# Doug.net
KiCad netlist of a schematic drawn in EAGLE
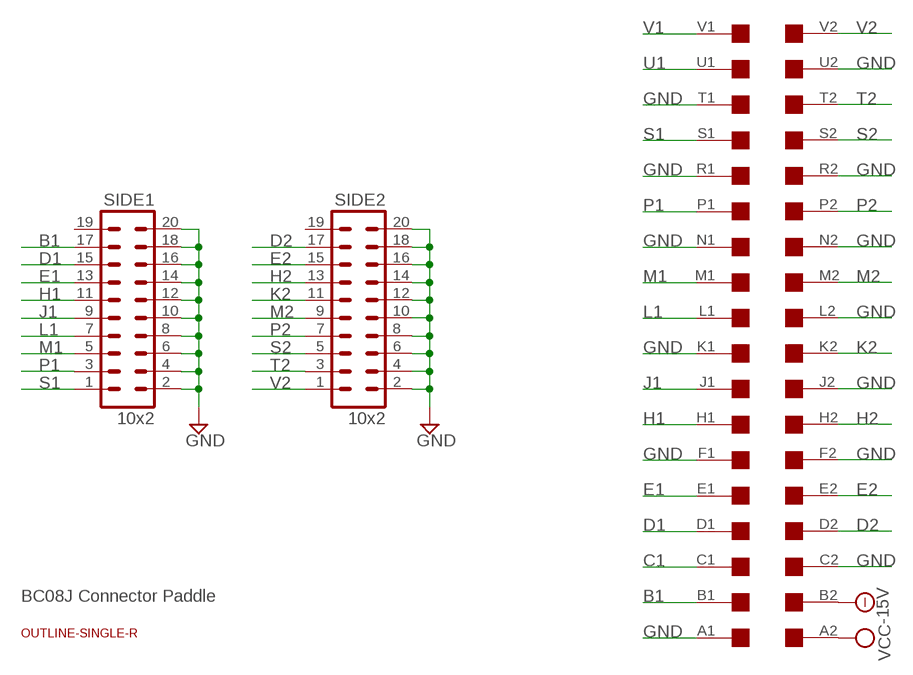
[diagram p0: schematic, sheet 1]

(export (version "E")
  (design (tool "Eeschema 10.0.6"))
  (components
    (comp (ref "SIDE1")
      (value "10x2")
      (footprint "eagle-import:MA10-2")
      (libsource (lib "eagle-import") (part "MA10-2"))
    )
    (comp (ref "SIDE2")
      (value "10x2")
      (footprint "eagle-import:MA10-2")
      (libsource (lib "eagle-import") (part "MA10-2"))
    )
    (comp (ref "U$1")
      (value "OUTLINE-SINGLE-R")
      (footprint "eagle-import:SINGLE-R")
      (libsource (lib "eagle-import") (part "OUTLINE-SINGLE-R"))
    )
    (comp (ref "U$2")
      (value "EDGE")
      (footprint "eagle-import:EDGE-CON2")
      (libsource (lib "eagle-import") (part "SINGLE"))
    )
  )
  (nets
    (net (code "1") (name "-15V") (class "Default")
      (node (ref "U$2") (pin "B2") (pinfunction "1_B2") (pintype "bidirectional"))
    )
    (net (code "2") (name "/B1") (class "Default")
      (node (ref "SIDE1") (pin "17") (pinfunction "17_17") (pintype "passive"))
      (node (ref "U$2") (pin "B1") (pinfunction "1_B1") (pintype "bidirectional"))
    )
    (net (code "3") (name "/C1") (class "Default")
      (node (ref "U$2") (pin "C1") (pinfunction "1_C1") (pintype "bidirectional"))
    )
    (net (code "4") (name "/D1") (class "Default")
      (node (ref "SIDE1") (pin "15") (pinfunction "15_15") (pintype "passive"))
      (node (ref "U$2") (pin "D1") (pinfunction "1_D1") (pintype "bidirectional"))
    )
    (net (code "5") (name "/D2") (class "Default")
      (node (ref "SIDE2") (pin "17") (pinfunction "17_17") (pintype "passive"))
      (node (ref "U$2") (pin "D2") (pinfunction "1_D2") (pintype "bidirectional"))
    )
    (net (code "6") (name "/E1") (class "Default")
      (node (ref "SIDE1") (pin "13") (pinfunction "13_13") (pintype "passive"))
      (node (ref "U$2") (pin "E1") (pinfunction "1_E1") (pintype "bidirectional"))
    )
    (net (code "7") (name "/E2") (class "Default")
      (node (ref "SIDE2") (pin "15") (pinfunction "15_15") (pintype "passive"))
      (node (ref "U$2") (pin "E2") (pinfunction "1_E2") (pintype "bidirectional"))
    )
    (net (code "8") (name "/H1") (class "Default")
      (node (ref "SIDE1") (pin "11") (pinfunction "11_11") (pintype "passive"))
      (node (ref "U$2") (pin "H1") (pinfunction "1_H1") (pintype "bidirectional"))
    )
    (net (code "9") (name "/H2") (class "Default")
      (node (ref "SIDE2") (pin "13") (pinfunction "13_13") (pintype "passive"))
      (node (ref "U$2") (pin "H2") (pinfunction "1_H2") (pintype "bidirectional"))
    )
    (net (code "10") (name "/J1") (class "Default")
      (node (ref "SIDE1") (pin "9") (pinfunction "9_9") (pintype "passive"))
      (node (ref "U$2") (pin "J1") (pinfunction "1_J1") (pintype "bidirectional"))
    )
    (net (code "11") (name "/K2") (class "Default")
      (node (ref "SIDE2") (pin "11") (pinfunction "11_11") (pintype "passive"))
      (node (ref "U$2") (pin "K2") (pinfunction "1_K2") (pintype "bidirectional"))
    )
    (net (code "12") (name "/L1") (class "Default")
      (node (ref "SIDE1") (pin "7") (pinfunction "7_7") (pintype "passive"))
      (node (ref "U$2") (pin "L1") (pinfunction "1_L1") (pintype "bidirectional"))
    )
    (net (code "13") (name "/M1") (class "Default")
      (node (ref "SIDE1") (pin "5") (pinfunction "5_5") (pintype "passive"))
      (node (ref "U$2") (pin "M1") (pinfunction "1_M1") (pintype "bidirectional"))
    )
    (net (code "14") (name "/M2") (class "Default")
      (node (ref "SIDE2") (pin "9") (pinfunction "9_9") (pintype "passive"))
      (node (ref "U$2") (pin "M2") (pinfunction "1_M2") (pintype "bidirectional"))
    )
    (net (code "15") (name "/P1") (class "Default")
      (node (ref "SIDE1") (pin "3") (pinfunction "3_3") (pintype "passive"))
      (node (ref "U$2") (pin "P1") (pinfunction "1_P1") (pintype "bidirectional"))
    )
    (net (code "16") (name "/P2") (class "Default")
      (node (ref "SIDE2") (pin "7") (pinfunction "7_7") (pintype "passive"))
      (node (ref "U$2") (pin "P2") (pinfunction "1_P2") (pintype "bidirectional"))
    )
    (net (code "17") (name "/S1") (class "Default")
      (node (ref "SIDE1") (pin "1") (pinfunction "1_1") (pintype "passive"))
      (node (ref "U$2") (pin "S1") (pinfunction "1_S1") (pintype "bidirectional"))
    )
    (net (code "18") (name "/S2") (class "Default")
      (node (ref "SIDE2") (pin "5") (pinfunction "5_5") (pintype "passive"))
      (node (ref "U$2") (pin "S2") (pinfunction "1_S2") (pintype "bidirectional"))
    )
    (net (code "19") (name "/T2") (class "Default")
      (node (ref "SIDE2") (pin "3") (pinfunction "3_3") (pintype "passive"))
      (node (ref "U$2") (pin "T2") (pinfunction "1_T2") (pintype "bidirectional"))
    )
    (net (code "20") (name "/U1") (class "Default")
      (node (ref "U$2") (pin "U1") (pinfunction "1_U1") (pintype "bidirectional"))
    )
    (net (code "21") (name "/V1") (class "Default")
      (node (ref "U$2") (pin "V1") (pinfunction "1_V1") (pintype "bidirectional"))
    )
    (net (code "22") (name "/V2") (class "Default")
      (node (ref "SIDE2") (pin "1") (pinfunction "1_1") (pintype "passive"))
      (node (ref "U$2") (pin "V2") (pinfunction "1_V2") (pintype "bidirectional"))
    )
    (net (code "23") (name "GND") (class "Default")
      (node (ref "SIDE1") (pin "10") (pinfunction "10_10") (pintype "passive"))
      (node (ref "SIDE1") (pin "12") (pinfunction "12_12") (pintype "passive"))
      (node (ref "SIDE1") (pin "14") (pinfunction "14_14") (pintype "passive"))
      (node (ref "SIDE1") (pin "16") (pinfunction "16_16") (pintype "passive"))
      (node (ref "SIDE1") (pin "18") (pinfunction "18_18") (pintype "passive"))
      (node (ref "SIDE1") (pin "2") (pinfunction "2_2") (pintype "passive"))
      (node (ref "SIDE1") (pin "20") (pinfunction "20_20") (pintype "passive"))
      (node (ref "SIDE1") (pin "4") (pinfunction "4_4") (pintype "passive"))
      (node (ref "SIDE1") (pin "6") (pinfunction "6_6") (pintype "passive"))
      (node (ref "SIDE1") (pin "8") (pinfunction "8_8") (pintype "passive"))
      (node (ref "SIDE2") (pin "10") (pinfunction "10_10") (pintype "passive"))
      (node (ref "SIDE2") (pin "12") (pinfunction "12_12") (pintype "passive"))
      (node (ref "SIDE2") (pin "14") (pinfunction "14_14") (pintype "passive"))
      (node (ref "SIDE2") (pin "16") (pinfunction "16_16") (pintype "passive"))
      (node (ref "SIDE2") (pin "18") (pinfunction "18_18") (pintype "passive"))
      (node (ref "SIDE2") (pin "2") (pinfunction "2_2") (pintype "passive"))
      (node (ref "SIDE2") (pin "20") (pinfunction "20_20") (pintype "passive"))
      (node (ref "SIDE2") (pin "4") (pinfunction "4_4") (pintype "passive"))
      (node (ref "SIDE2") (pin "6") (pinfunction "6_6") (pintype "passive"))
      (node (ref "SIDE2") (pin "8") (pinfunction "8_8") (pintype "passive"))
      (node (ref "U$2") (pin "A1") (pinfunction "1_A1") (pintype "bidirectional"))
      (node (ref "U$2") (pin "C2") (pinfunction "1_C2") (pintype "bidirectional"))
      (node (ref "U$2") (pin "F1") (pinfunction "1_F1") (pintype "bidirectional"))
      (node (ref "U$2") (pin "F2") (pinfunction "1_F2") (pintype "bidirectional"))
      (node (ref "U$2") (pin "J2") (pinfunction "1_J2") (pintype "bidirectional"))
      (node (ref "U$2") (pin "K1") (pinfunction "1_K1") (pintype "bidirectional"))
      (node (ref "U$2") (pin "L2") (pinfunction "1_L2") (pintype "bidirectional"))
      (node (ref "U$2") (pin "N1") (pinfunction "1_N1") (pintype "bidirectional"))
      (node (ref "U$2") (pin "N2") (pinfunction "1_N2") (pintype "bidirectional"))
      (node (ref "U$2") (pin "R1") (pinfunction "1_R1") (pintype "bidirectional"))
      (node (ref "U$2") (pin "R2") (pinfunction "1_R2") (pintype "bidirectional"))
      (node (ref "U$2") (pin "T1") (pinfunction "1_T1") (pintype "bidirectional"))
      (node (ref "U$2") (pin "U2") (pinfunction "1_U2") (pintype "bidirectional"))
    )
    (net (code "24") (name "VCC") (class "Default")
      (node (ref "U$2") (pin "A2") (pinfunction "1_A2") (pintype "bidirectional"))
    )
    (net (code "25") (name "unconnected-(SIDE1-Pad19)") (class "Default")
      (node (ref "SIDE1") (pin "19") (pinfunction "19_19") (pintype "passive"))
    )
    (net (code "26") (name "unconnected-(SIDE2-Pad19)") (class "Default")
      (node (ref "SIDE2") (pin "19") (pinfunction "19_19") (pintype "passive"))
    )
  )
)
